# relay-simple.net
KiCad netlist of a schematic drawn in EAGLE
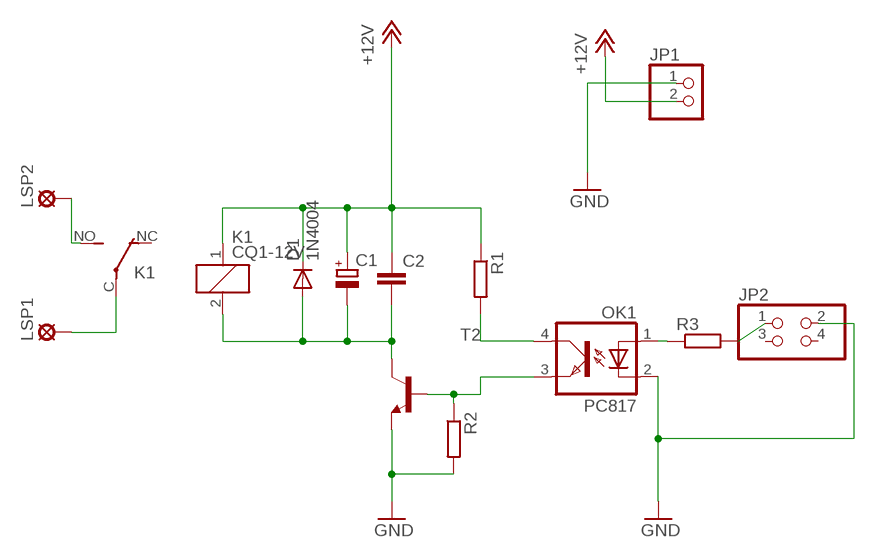
[diagram p0: schematic, sheet 1]

(export (version "E")
  (design (tool "Eeschema 10.0.6"))
  (components
    (comp (ref "C1")
      (value "CPOL-EUE2-5")
      (footprint "eagle-import:E2-5")
      (libsource (lib "eagle-import") (part "CPOL-EUE2-5"))
    )
    (comp (ref "C2")
      (value "C-EUC1206")
      (footprint "eagle-import:C1206")
      (libsource (lib "eagle-import") (part "C-EUC1206"))
    )
    (comp (ref "D1")
      (value "1N4004")
      (footprint "eagle-import:DO41-10")
      (libsource (lib "eagle-import") (part "1N4004"))
    )
    (comp (ref "JP1")
      (value "PINHD-1X2")
      (footprint "eagle-import:1X02")
      (libsource (lib "eagle-import") (part "PINHD-1X2"))
    )
    (comp (ref "JP2")
      (value "PINHD-2X2")
      (footprint "eagle-import:2X02")
      (libsource (lib "eagle-import") (part "PINHD-2X2"))
    )
    (comp (ref "K1")
      (value "CQ1-12V")
      (footprint "eagle-import:CQ1")
      (libsource (lib "eagle-import") (part "CQ1-12V"))
    )
    (comp (ref "LSP1")
      (value "LSP10")
      (footprint "eagle-import:LSP10")
      (libsource (lib "eagle-import") (part "LSP10"))
    )
    (comp (ref "LSP2")
      (value "LSP10")
      (footprint "eagle-import:LSP10")
      (libsource (lib "eagle-import") (part "LSP10"))
    )
    (comp (ref "OK1")
      (value "PC817")
      (footprint "eagle-import:DIL04")
      (fields (field (name "MPN") "PC817X4J000F"))
      (libsource (lib "eagle-import") (part "PC817"))
    )
    (comp (ref "R1")
      (value "R-EU_R1206")
      (footprint "eagle-import:R1206")
      (libsource (lib "eagle-import") (part "R-EU_R1206"))
    )
    (comp (ref "R2")
      (value "R-EU_R1206")
      (footprint "eagle-import:R1206")
      (libsource (lib "eagle-import") (part "R-EU_R1206"))
    )
    (comp (ref "R3")
      (value "R-EU_R1206")
      (footprint "eagle-import:R1206")
      (libsource (lib "eagle-import") (part "R-EU_R1206"))
    )
    (comp (ref "T2")
      (value "-NPN-TO92")
      (footprint "eagle-import:TO92")
      (libsource (lib "eagle-import") (part "-NPN-TO92"))
    )
  )
  (nets
    (net (code "1") (name "+12V") (class "Default")
      (node (ref "C1") (pin "+") (pinfunction "+_+") (pintype "passive"))
      (node (ref "C2") (pin "1") (pinfunction "1_1") (pintype "passive"))
      (node (ref "D1") (pin "C") (pinfunction "C_C") (pintype "passive"))
      (node (ref "JP1") (pin "2") (pinfunction "2_2") (pintype "passive"))
      (node (ref "K1") (pin "1") (pinfunction "1_1") (pintype "passive"))
      (node (ref "R1") (pin "1") (pinfunction "1_1") (pintype "passive"))
    )
    (net (code "2") (name "GND") (class "Default")
      (node (ref "JP1") (pin "1") (pinfunction "1_1") (pintype "passive"))
      (node (ref "JP2") (pin "2") (pinfunction "2_2") (pintype "passive"))
      (node (ref "OK1") (pin "2") (pinfunction "C_2") (pintype "passive"))
      (node (ref "R2") (pin "2") (pinfunction "2_2") (pintype "passive"))
      (node (ref "T2") (pin "1") (pinfunction "E_1") (pintype "passive"))
    )
    (net (code "3") (name "Net-(JP2-Pad1)") (class "Default")
      (node (ref "JP2") (pin "1") (pinfunction "1_1") (pintype "passive"))
      (node (ref "R3") (pin "2") (pinfunction "2_2") (pintype "passive"))
    )
    (net (code "4") (name "Net-(K1B-P)") (class "Default")
      (node (ref "K1") (pin "C") (pinfunction "P_C") (pintype "passive"))
      (node (ref "LSP1") (pin "MP") (pinfunction "MP_MP") (pintype "passive"))
    )
    (net (code "5") (name "Net-(K1B-S)") (class "Default")
      (node (ref "K1") (pin "NO") (pinfunction "S_NO") (pintype "passive"))
      (node (ref "LSP2") (pin "MP") (pinfunction "MP_MP") (pintype "passive"))
    )
    (net (code "6") (name "Net-(OK1-A)") (class "Default")
      (node (ref "OK1") (pin "1") (pinfunction "A_1") (pintype "passive"))
      (node (ref "R3") (pin "1") (pinfunction "1_1") (pintype "passive"))
    )
    (net (code "7") (name "Net-(OK1-COL)") (class "Default")
      (node (ref "OK1") (pin "4") (pinfunction "COL_4") (pintype "passive"))
      (node (ref "R1") (pin "2") (pinfunction "2_2") (pintype "passive"))
    )
    (net (code "8") (name "Net-(OK1-EMIT)") (class "Default")
      (node (ref "OK1") (pin "3") (pinfunction "EMIT_3") (pintype "passive"))
      (node (ref "R2") (pin "1") (pinfunction "1_1") (pintype "passive"))
      (node (ref "T2") (pin "2") (pinfunction "B_2") (pintype "passive"))
    )
    (net (code "9") (name "Net-(T2-C)") (class "Default")
      (node (ref "C1") (pin "-") (pinfunction "-_-") (pintype "passive"))
      (node (ref "C2") (pin "2") (pinfunction "2_2") (pintype "passive"))
      (node (ref "D1") (pin "A") (pinfunction "A_A") (pintype "passive"))
      (node (ref "K1") (pin "2") (pinfunction "2_2") (pintype "passive"))
      (node (ref "T2") (pin "3") (pinfunction "C_3") (pintype "passive"))
    )
    (net (code "10") (name "unconnected-(JP2-Pad3)") (class "Default")
      (node (ref "JP2") (pin "3") (pinfunction "3_3") (pintype "passive"))
    )
    (net (code "11") (name "unconnected-(JP2-Pad4)") (class "Default")
      (node (ref "JP2") (pin "4") (pinfunction "4_4") (pintype "passive"))
    )
    (net (code "12") (name "unconnected-(K1B-O-PadNC)") (class "Default")
      (node (ref "K1") (pin "NC") (pinfunction "O_NC") (pintype "passive"))
    )
  )
)
